# P_11__CPU_IO.net
KiCad netlist of a schematic drawn in Altium Designer
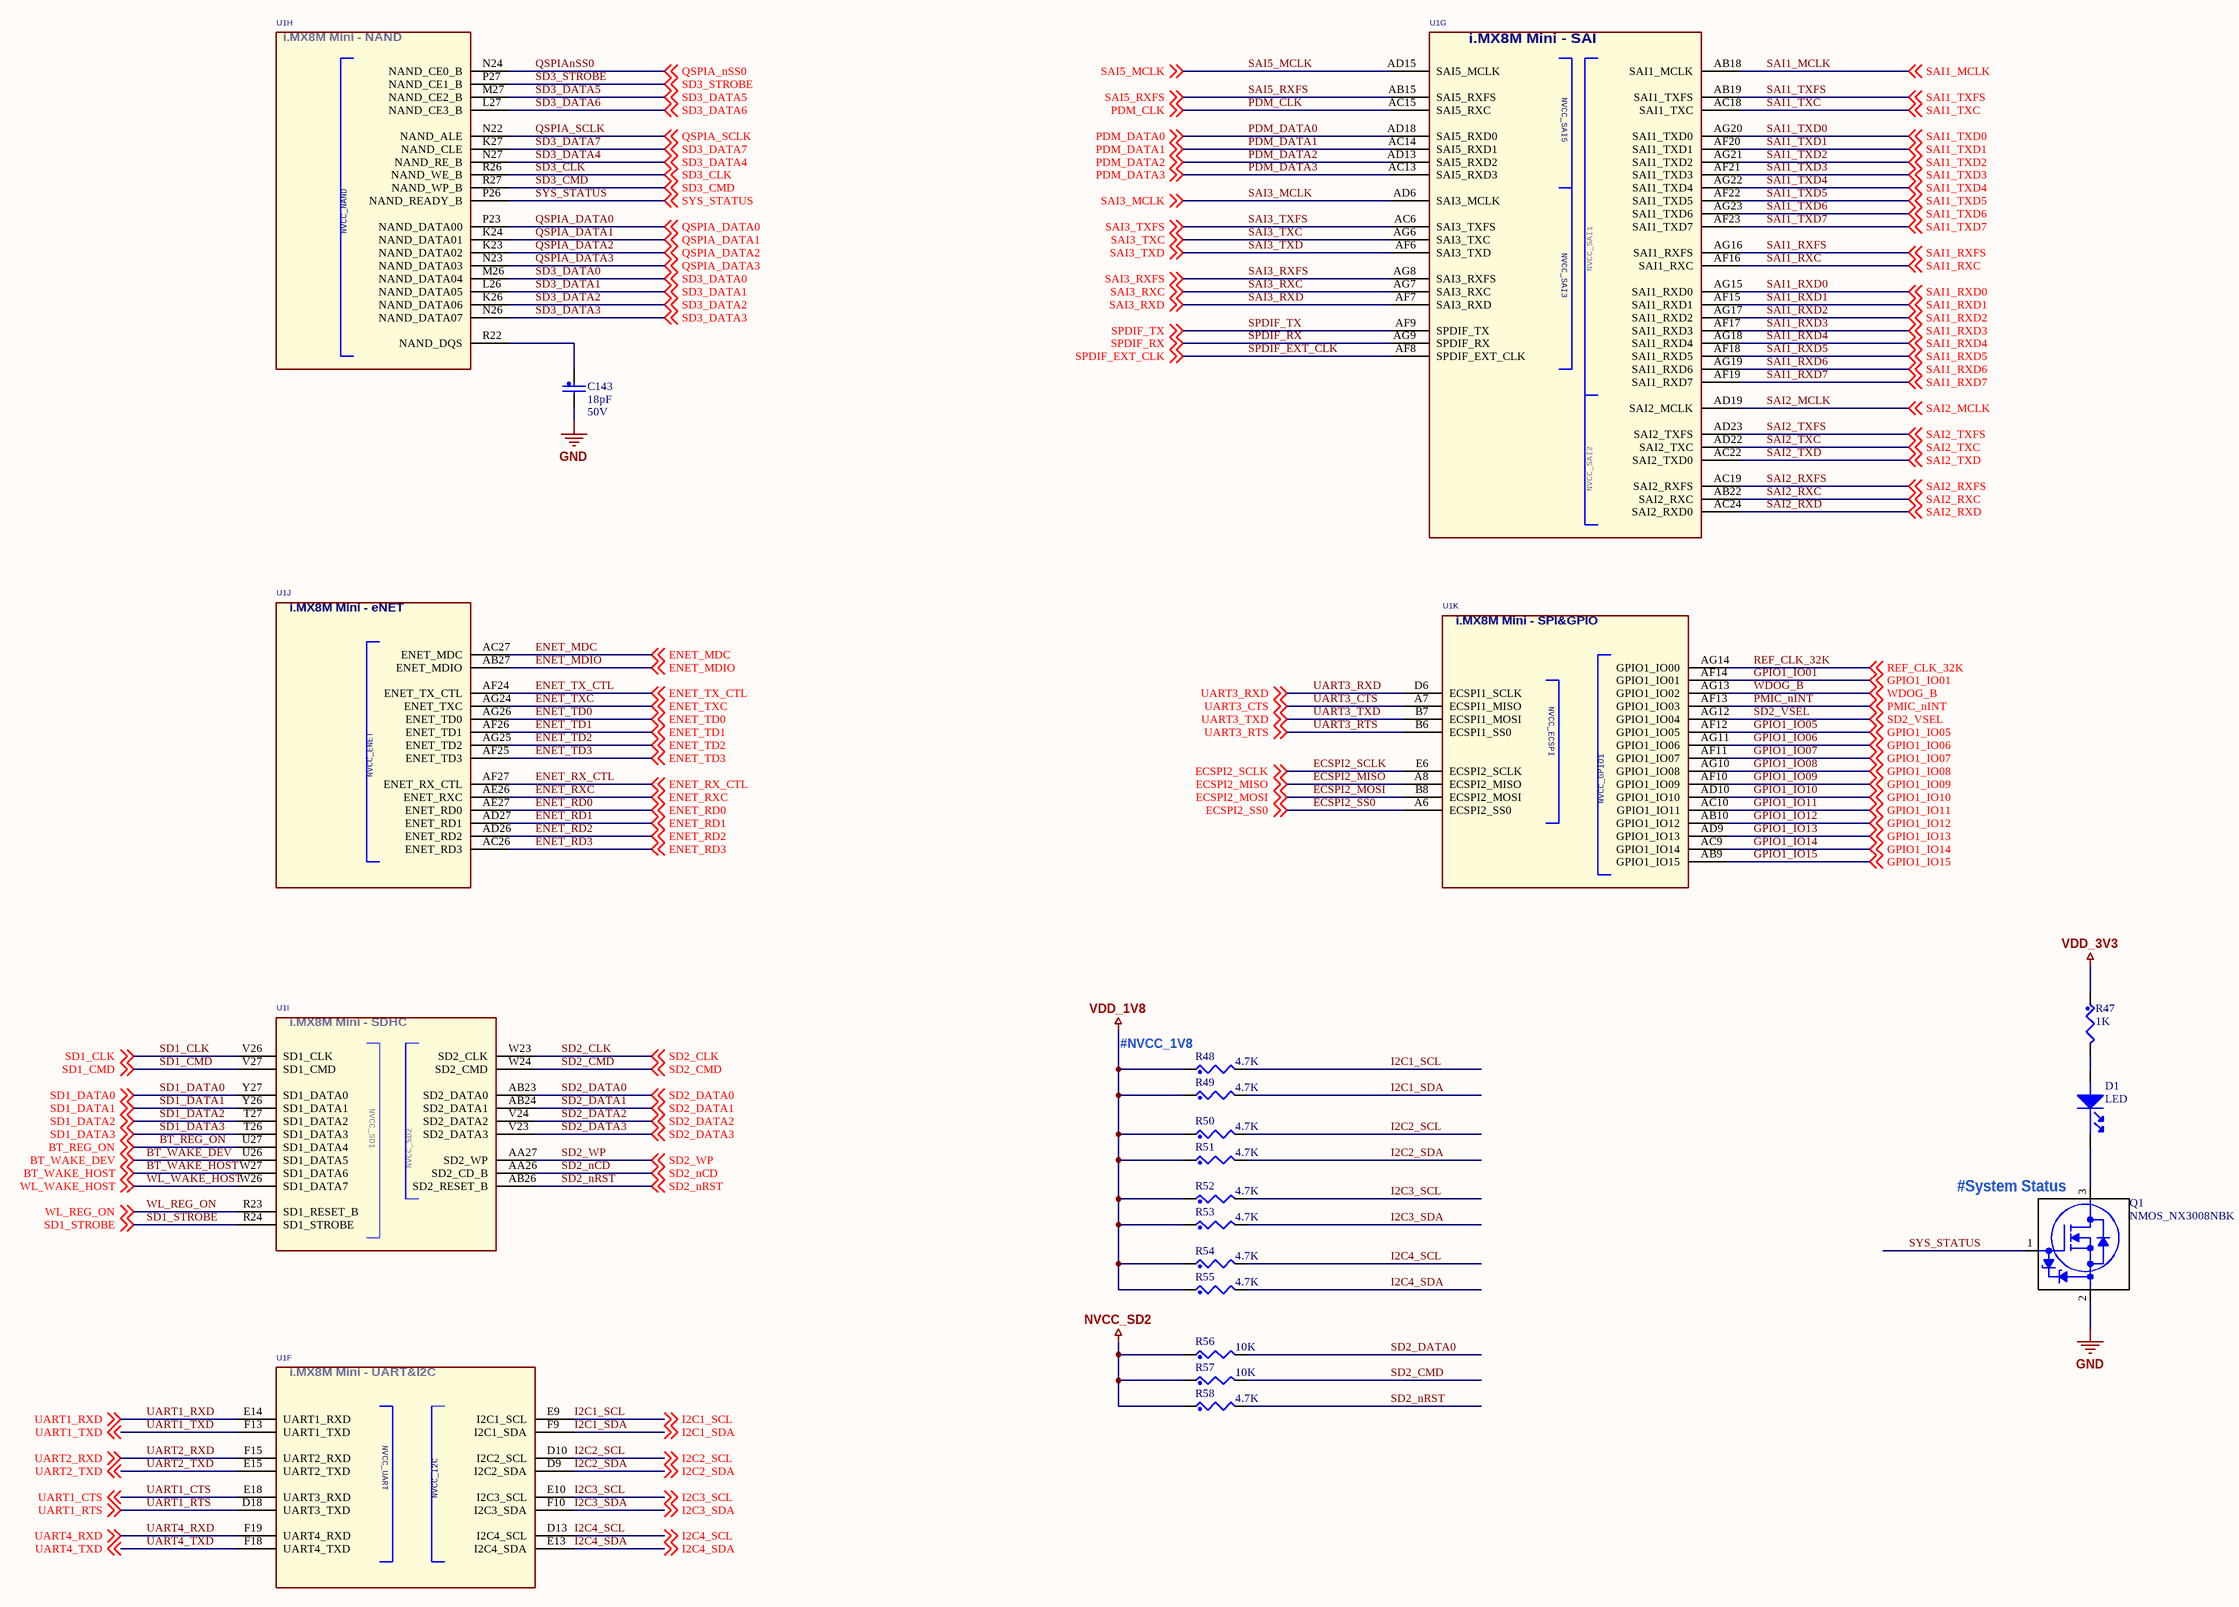
[diagram p0: P[11]_CPU_IO.SchDoc]

(export (version "E")
  (design (tool "Eeschema 10.0.6"))
  (components
    (comp (ref "C143")
      (value "18pF")
      (footprint "0201_CC - C")
      (fields (field (name "VOLTAGE") "50V"))
      (libsource (lib "AA_iMX8_M_") (part "CAP_NP"))
    )
    (comp (ref "D1") (value "LED") (footprint "LED_0603") (libsource (lib "AA_iMX8_M_") (part "LED")))
    (comp (ref "Q1")
      (value "NMOS_NX3008NBK")
      (footprint "SOT65P210X110-3N")
      (description "NMOS_NX3008NBK\\AAR")
      (libsource (lib "AA_iMX8_M_") (part "NMOS_NX3008NBK"))
    )
    (comp (ref "R47") (value "1K") (footprint "0201_CC") (libsource (lib "AA_iMX8_M_") (part "RES")))
    (comp (ref "R48") (value "4.7K") (footprint "0201_CC") (libsource (lib "AA_iMX8_M_") (part "RES")))
    (comp (ref "R49") (value "4.7K") (footprint "0201_CC") (libsource (lib "AA_iMX8_M_") (part "RES")))
    (comp (ref "R50") (value "4.7K") (footprint "0201_CC") (libsource (lib "AA_iMX8_M_") (part "RES")))
    (comp (ref "R51") (value "4.7K") (footprint "0201_CC") (libsource (lib "AA_iMX8_M_") (part "RES")))
    (comp (ref "R52") (value "4.7K") (footprint "0201_CC") (libsource (lib "AA_iMX8_M_") (part "RES")))
    (comp (ref "R53") (value "4.7K") (footprint "0201_CC") (libsource (lib "AA_iMX8_M_") (part "RES")))
    (comp (ref "R54") (value "4.7K") (footprint "0201_CC") (libsource (lib "AA_iMX8_M_") (part "RES")))
    (comp (ref "R55") (value "4.7K") (footprint "0201_CC") (libsource (lib "AA_iMX8_M_") (part "RES")))
    (comp (ref "R56") (value "10K") (footprint "0201_CC") (libsource (lib "AA_iMX8_M_") (part "RES")))
    (comp (ref "R57") (value "10K") (footprint "0201_CC") (libsource (lib "AA_iMX8_M_") (part "RES")))
    (comp (ref "R58") (value "4.7K") (footprint "0201_CC") (libsource (lib "AA_iMX8_M_") (part "RES")))
    (comp (ref "U1")
      (value "SFP_CGND")
      (footprint "BGA486_0P5_14X14")
      (description "IC CPU QUAD CORTEX A53+M4 1.8GHZ BGA486 / By Arman Arvand")
      (libsource (lib "AA_iMX8_M_") (part "MIMX8MM_BGA486P"))
    )
  )
  (nets
    (net (code "1") (name "BT_REG_ON") (class "Default")
      (node (ref "U1") (pin "U27") (pinfunction "SD1_DATA4_U27") (pintype "passive"))
    )
    (net (code "2") (name "BT_WAKE_DEV") (class "Default")
      (node (ref "U1") (pin "U26") (pinfunction "SD1_DATA5_U26") (pintype "passive"))
    )
    (net (code "3") (name "BT_WAKE_HOST") (class "Default")
      (node (ref "U1") (pin "W27") (pinfunction "SD1_DATA6_W27") (pintype "passive"))
    )
    (net (code "4") (name "ECSPI2_MISO") (class "Default")
      (node (ref "U1") (pin "A8") (pinfunction "ECSPI2_MISO_A8") (pintype "passive"))
    )
    (net (code "5") (name "ECSPI2_MOSI") (class "Default")
      (node (ref "U1") (pin "B8") (pinfunction "ECSPI2_MOSI_B8") (pintype "passive"))
    )
    (net (code "6") (name "ECSPI2_SCLK") (class "Default")
      (node (ref "U1") (pin "E6") (pinfunction "ECSPI2_SCLK_E6") (pintype "passive"))
    )
    (net (code "7") (name "ECSPI2_SS0") (class "Default")
      (node (ref "U1") (pin "A6") (pinfunction "ECSPI2_SS0_A6") (pintype "passive"))
    )
    (net (code "8") (name "ENET_MDC") (class "Default")
      (node (ref "U1") (pin "AC27") (pinfunction "ENET_MDC_AC27") (pintype "passive"))
    )
    (net (code "9") (name "ENET_MDIO") (class "Default")
      (node (ref "U1") (pin "AB27") (pinfunction "ENET_MDIO_AB27") (pintype "passive"))
    )
    (net (code "10") (name "ENET_RD0") (class "Default")
      (node (ref "U1") (pin "AE27") (pinfunction "ENET_RD0_AE27") (pintype "passive"))
    )
    (net (code "11") (name "ENET_RD1") (class "Default")
      (node (ref "U1") (pin "AD27") (pinfunction "ENET_RD1_AD27") (pintype "passive"))
    )
    (net (code "12") (name "ENET_RD2") (class "Default")
      (node (ref "U1") (pin "AD26") (pinfunction "ENET_RD2_AD26") (pintype "passive"))
    )
    (net (code "13") (name "ENET_RD3") (class "Default")
      (node (ref "U1") (pin "AC26") (pinfunction "ENET_RD3_AC26") (pintype "passive"))
    )
    (net (code "14") (name "ENET_RXC") (class "Default")
      (node (ref "U1") (pin "AE26") (pinfunction "ENET_RXC_AE26") (pintype "passive"))
    )
    (net (code "15") (name "ENET_RX_CTL") (class "Default")
      (node (ref "U1") (pin "AF27") (pinfunction "ENET_RX_CTL_AF27") (pintype "passive"))
    )
    (net (code "16") (name "ENET_TD0") (class "Default")
      (node (ref "U1") (pin "AG26") (pinfunction "ENET_TD0_AG26") (pintype "passive"))
    )
    (net (code "17") (name "ENET_TD1") (class "Default")
      (node (ref "U1") (pin "AF26") (pinfunction "ENET_TD1_AF26") (pintype "passive"))
    )
    (net (code "18") (name "ENET_TD2") (class "Default")
      (node (ref "U1") (pin "AG25") (pinfunction "ENET_TD2_AG25") (pintype "passive"))
    )
    (net (code "19") (name "ENET_TD3") (class "Default")
      (node (ref "U1") (pin "AF25") (pinfunction "ENET_TD3_AF25") (pintype "passive"))
    )
    (net (code "20") (name "ENET_TXC") (class "Default")
      (node (ref "U1") (pin "AG24") (pinfunction "ENET_TXC_AG24") (pintype "passive"))
    )
    (net (code "21") (name "ENET_TX_CTL") (class "Default")
      (node (ref "U1") (pin "AF24") (pinfunction "ENET_TX_CTL_AF24") (pintype "passive"))
    )
    (net (code "22") (name "GND") (class "Default")
      (node (ref "C143") (pin "2") (pinfunction "2_2") (pintype "passive"))
      (node (ref "Q1") (pin "2") (pinfunction "SOURCE_2") (pintype "passive"))
    )
    (net (code "23") (name "GPIO1_IO01") (class "Default")
      (node (ref "U1") (pin "AF14") (pinfunction "GPIO1_IO01_AF14") (pintype "passive"))
    )
    (net (code "24") (name "GPIO1_IO05") (class "Default")
      (node (ref "U1") (pin "AF12") (pinfunction "GPIO1_IO05_AF12") (pintype "passive"))
    )
    (net (code "25") (name "GPIO1_IO06") (class "Default")
      (node (ref "U1") (pin "AG11") (pinfunction "GPIO1_IO06_AG11") (pintype "passive"))
    )
    (net (code "26") (name "GPIO1_IO07") (class "Default")
      (node (ref "U1") (pin "AF11") (pinfunction "GPIO1_IO07_AF11") (pintype "passive"))
    )
    (net (code "27") (name "GPIO1_IO08") (class "Default")
      (node (ref "U1") (pin "AG10") (pinfunction "GPIO1_IO08_AG10") (pintype "passive"))
    )
    (net (code "28") (name "GPIO1_IO09") (class "Default")
      (node (ref "U1") (pin "AF10") (pinfunction "GPIO1_IO09_AF10") (pintype "passive"))
    )
    (net (code "29") (name "GPIO1_IO10") (class "Default")
      (node (ref "U1") (pin "AD10") (pinfunction "GPIO1_IO10_AD10") (pintype "passive"))
    )
    (net (code "30") (name "GPIO1_IO11") (class "Default")
      (node (ref "U1") (pin "AC10") (pinfunction "GPIO1_IO11_AC10") (pintype "passive"))
    )
    (net (code "31") (name "GPIO1_IO12") (class "Default")
      (node (ref "U1") (pin "AB10") (pinfunction "GPIO1_IO12_AB10") (pintype "passive"))
    )
    (net (code "32") (name "GPIO1_IO13") (class "Default")
      (node (ref "U1") (pin "AD9") (pinfunction "GPIO1_IO13_AD9") (pintype "passive"))
    )
    (net (code "33") (name "GPIO1_IO14") (class "Default")
      (node (ref "U1") (pin "AC9") (pinfunction "GPIO1_IO14_AC9") (pintype "passive"))
    )
    (net (code "34") (name "GPIO1_IO15") (class "Default")
      (node (ref "U1") (pin "AB9") (pinfunction "GPIO1_IO15_AB9") (pintype "passive"))
    )
    (net (code "35") (name "I2C1_SCL") (class "Default")
      (node (ref "R48") (pin "2") (pinfunction "2_2") (pintype "passive"))
      (node (ref "U1") (pin "E9") (pinfunction "I2C1_SCL_E9") (pintype "passive"))
    )
    (net (code "36") (name "I2C1_SDA") (class "Default")
      (node (ref "R49") (pin "2") (pinfunction "2_2") (pintype "passive"))
      (node (ref "U1") (pin "F9") (pinfunction "I2C1_SDA_F9") (pintype "passive"))
    )
    (net (code "37") (name "I2C2_SCL") (class "Default")
      (node (ref "R50") (pin "2") (pinfunction "2_2") (pintype "passive"))
      (node (ref "U1") (pin "D10") (pinfunction "I2C2_SCL_D10") (pintype "passive"))
    )
    (net (code "38") (name "I2C2_SDA") (class "Default")
      (node (ref "R51") (pin "2") (pinfunction "2_2") (pintype "passive"))
      (node (ref "U1") (pin "D9") (pinfunction "I2C2_SDA_D9") (pintype "passive"))
    )
    (net (code "39") (name "I2C3_SCL") (class "Default")
      (node (ref "R52") (pin "2") (pinfunction "2_2") (pintype "passive"))
      (node (ref "U1") (pin "E10") (pinfunction "I2C3_SCL_E10") (pintype "passive"))
    )
    (net (code "40") (name "I2C3_SDA") (class "Default")
      (node (ref "R53") (pin "2") (pinfunction "2_2") (pintype "passive"))
      (node (ref "U1") (pin "F10") (pinfunction "I2C3_SDA_F10") (pintype "passive"))
    )
    (net (code "41") (name "I2C4_SCL") (class "Default")
      (node (ref "R54") (pin "2") (pinfunction "2_2") (pintype "passive"))
      (node (ref "U1") (pin "D13") (pinfunction "I2C4_SCL_D13") (pintype "passive"))
    )
    (net (code "42") (name "I2C4_SDA") (class "Default")
      (node (ref "R55") (pin "2") (pinfunction "2_2") (pintype "passive"))
      (node (ref "U1") (pin "E13") (pinfunction "I2C4_SDA_E13") (pintype "passive"))
    )
    (net (code "43") (name "NVCC_SD2") (class "Default")
      (node (ref "R56") (pin "1") (pinfunction "1_1") (pintype "passive"))
      (node (ref "R57") (pin "1") (pinfunction "1_1") (pintype "passive"))
      (node (ref "R58") (pin "1") (pinfunction "1_1") (pintype "passive"))
    )
    (net (code "44") (name "Net-(D1-ANODE)") (class "Default")
      (node (ref "D1") (pin "A") (pinfunction "ANODE_A") (pintype "passive"))
      (node (ref "R47") (pin "2") (pinfunction "2_2") (pintype "passive"))
    )
    (net (code "45") (name "Net-(D1-CATHODE)") (class "Default")
      (node (ref "D1") (pin "C") (pinfunction "CATHODE_C") (pintype "passive"))
      (node (ref "Q1") (pin "3") (pinfunction "DRAIN_3") (pintype "passive"))
    )
    (net (code "46") (name "Net-(U1H-NAND_DQS)") (class "Default")
      (node (ref "C143") (pin "1") (pinfunction "1_1") (pintype "passive"))
      (node (ref "U1") (pin "R22") (pinfunction "NAND_DQS_R22") (pintype "passive"))
    )
    (net (code "47") (name "PDM_CLK") (class "Default")
      (node (ref "U1") (pin "AC15") (pinfunction "SAI5_RXC_AC15") (pintype "passive"))
    )
    (net (code "48") (name "PDM_DATA0") (class "Default")
      (node (ref "U1") (pin "AD18") (pinfunction "SAI5_RXD0_AD18") (pintype "passive"))
    )
    (net (code "49") (name "PDM_DATA1") (class "Default")
      (node (ref "U1") (pin "AC14") (pinfunction "SAI5_RXD1_AC14") (pintype "passive"))
    )
    (net (code "50") (name "PDM_DATA2") (class "Default")
      (node (ref "U1") (pin "AD13") (pinfunction "SAI5_RXD2_AD13") (pintype "passive"))
    )
    (net (code "51") (name "PDM_DATA3") (class "Default")
      (node (ref "U1") (pin "AC13") (pinfunction "SAI5_RXD3_AC13") (pintype "passive"))
    )
    (net (code "52") (name "PMIC_nINT") (class "Default")
      (node (ref "U1") (pin "AF13") (pinfunction "GPIO1_IO03_AF13") (pintype "passive"))
    )
    (net (code "53") (name "QSPIA_DATA0") (class "Default")
      (node (ref "U1") (pin "P23") (pinfunction "NAND_DATA00_P23") (pintype "passive"))
    )
    (net (code "54") (name "QSPIA_DATA1") (class "Default")
      (node (ref "U1") (pin "K24") (pinfunction "NAND_DATA01_K24") (pintype "passive"))
    )
    (net (code "55") (name "QSPIA_DATA2") (class "Default")
      (node (ref "U1") (pin "K23") (pinfunction "NAND_DATA02_K23") (pintype "passive"))
    )
    (net (code "56") (name "QSPIA_DATA3") (class "Default")
      (node (ref "U1") (pin "N23") (pinfunction "NAND_DATA03_N23") (pintype "passive"))
    )
    (net (code "57") (name "QSPIA_SCLK") (class "Default")
      (node (ref "U1") (pin "N22") (pinfunction "NAND_ALE_N22") (pintype "passive"))
    )
    (net (code "58") (name "QSPIA_nSS0") (class "Default")
      (node (ref "U1") (pin "N24") (pinfunction "NAND_CE0_B_N24") (pintype "passive"))
    )
    (net (code "59") (name "REF_CLK_32K") (class "Default")
      (node (ref "U1") (pin "AG14") (pinfunction "GPIO1_IO00_AG14") (pintype "passive"))
    )
    (net (code "60") (name "SAI1_MCLK") (class "Default")
      (node (ref "U1") (pin "AB18") (pinfunction "SAI1_MCLK_AB18") (pintype "passive"))
    )
    (net (code "61") (name "SAI1_RXC") (class "Default")
      (node (ref "U1") (pin "AF16") (pinfunction "SAI1_RXC_AF16") (pintype "passive"))
    )
    (net (code "62") (name "SAI1_RXD0") (class "Default")
      (node (ref "U1") (pin "AG15") (pinfunction "SAI1_RXD0_AG15") (pintype "passive"))
    )
    (net (code "63") (name "SAI1_RXD1") (class "Default")
      (node (ref "U1") (pin "AF15") (pinfunction "SAI1_RXD1_AF15") (pintype "passive"))
    )
    (net (code "64") (name "SAI1_RXD2") (class "Default")
      (node (ref "U1") (pin "AG17") (pinfunction "SAI1_RXD2_AG17") (pintype "passive"))
    )
    (net (code "65") (name "SAI1_RXD3") (class "Default")
      (node (ref "U1") (pin "AF17") (pinfunction "SAI1_RXD3_AF17") (pintype "passive"))
    )
    (net (code "66") (name "SAI1_RXD4") (class "Default")
      (node (ref "U1") (pin "AG18") (pinfunction "SAI1_RXD4_AG18") (pintype "passive"))
    )
    (net (code "67") (name "SAI1_RXD5") (class "Default")
      (node (ref "U1") (pin "AF18") (pinfunction "SAI1_RXD5_AF18") (pintype "passive"))
    )
    (net (code "68") (name "SAI1_RXD6") (class "Default")
      (node (ref "U1") (pin "AG19") (pinfunction "SAI1_RXD6_AG19") (pintype "passive"))
    )
    (net (code "69") (name "SAI1_RXD7") (class "Default")
      (node (ref "U1") (pin "AF19") (pinfunction "SAI1_RXD7_AF19") (pintype "passive"))
    )
    (net (code "70") (name "SAI1_RXFS") (class "Default")
      (node (ref "U1") (pin "AG16") (pinfunction "SAI1_RXFS_AG16") (pintype "passive"))
    )
    (net (code "71") (name "SAI1_TXC") (class "Default")
      (node (ref "U1") (pin "AC18") (pinfunction "SAI1_TXC_AC18") (pintype "passive"))
    )
    (net (code "72") (name "SAI1_TXD0") (class "Default")
      (node (ref "U1") (pin "AG20") (pinfunction "SAI1_TXD0_AG20") (pintype "passive"))
    )
    (net (code "73") (name "SAI1_TXD1") (class "Default")
      (node (ref "U1") (pin "AF20") (pinfunction "SAI1_TXD1_AF20") (pintype "passive"))
    )
    (net (code "74") (name "SAI1_TXD2") (class "Default")
      (node (ref "U1") (pin "AG21") (pinfunction "SAI1_TXD2_AG21") (pintype "passive"))
    )
    (net (code "75") (name "SAI1_TXD3") (class "Default")
      (node (ref "U1") (pin "AF21") (pinfunction "SAI1_TXD3_AF21") (pintype "passive"))
    )
    (net (code "76") (name "SAI1_TXD4") (class "Default")
      (node (ref "U1") (pin "AG22") (pinfunction "SAI1_TXD4_AG22") (pintype "passive"))
    )
    (net (code "77") (name "SAI1_TXD5") (class "Default")
      (node (ref "U1") (pin "AF22") (pinfunction "SAI1_TXD5_AF22") (pintype "passive"))
    )
    (net (code "78") (name "SAI1_TXD6") (class "Default")
      (node (ref "U1") (pin "AG23") (pinfunction "SAI1_TXD6_AG23") (pintype "passive"))
    )
    (net (code "79") (name "SAI1_TXD7") (class "Default")
      (node (ref "U1") (pin "AF23") (pinfunction "SAI1_TXD7_AF23") (pintype "passive"))
    )
    (net (code "80") (name "SAI1_TXFS") (class "Default")
      (node (ref "U1") (pin "AB19") (pinfunction "SAI1_TXFS_AB19") (pintype "passive"))
    )
    (net (code "81") (name "SAI2_MCLK") (class "Default")
      (node (ref "U1") (pin "AD19") (pinfunction "SAI2_MCLK_AD19") (pintype "passive"))
    )
    (net (code "82") (name "SAI2_RXC") (class "Default")
      (node (ref "U1") (pin "AB22") (pinfunction "SAI2_RXC_AB22") (pintype "passive"))
    )
    (net (code "83") (name "SAI2_RXD") (class "Default")
      (node (ref "U1") (pin "AC24") (pinfunction "SAI2_RXD0_AC24") (pintype "passive"))
    )
    (net (code "84") (name "SAI2_RXFS") (class "Default")
      (node (ref "U1") (pin "AC19") (pinfunction "SAI2_RXFS_AC19") (pintype "passive"))
    )
    (net (code "85") (name "SAI2_TXC") (class "Default")
      (node (ref "U1") (pin "AD22") (pinfunction "SAI2_TXC_AD22") (pintype "passive"))
    )
    (net (code "86") (name "SAI2_TXD") (class "Default")
      (node (ref "U1") (pin "AC22") (pinfunction "SAI2_TXD0_AC22") (pintype "passive"))
    )
    (net (code "87") (name "SAI2_TXFS") (class "Default")
      (node (ref "U1") (pin "AD23") (pinfunction "SAI2_TXFS_AD23") (pintype "passive"))
    )
    (net (code "88") (name "SAI3_MCLK") (class "Default")
      (node (ref "U1") (pin "AD6") (pinfunction "SAI3_MCLK_AD6") (pintype "passive"))
    )
    (net (code "89") (name "SAI3_RXC") (class "Default")
      (node (ref "U1") (pin "AG7") (pinfunction "SAI3_RXC_AG7") (pintype "passive"))
    )
    (net (code "90") (name "SAI3_RXD") (class "Default")
      (node (ref "U1") (pin "AF7") (pinfunction "SAI3_RXD_AF7") (pintype "passive"))
    )
    (net (code "91") (name "SAI3_RXFS") (class "Default")
      (node (ref "U1") (pin "AG8") (pinfunction "SAI3_RXFS_AG8") (pintype "passive"))
    )
    (net (code "92") (name "SAI3_TXC") (class "Default")
      (node (ref "U1") (pin "AG6") (pinfunction "SAI3_TXC_AG6") (pintype "passive"))
    )
    (net (code "93") (name "SAI3_TXD") (class "Default")
      (node (ref "U1") (pin "AF6") (pinfunction "SAI3_TXD_AF6") (pintype "passive"))
    )
    (net (code "94") (name "SAI3_TXFS") (class "Default")
      (node (ref "U1") (pin "AC6") (pinfunction "SAI3_TXFS_AC6") (pintype "passive"))
    )
    (net (code "95") (name "SAI5_MCLK") (class "Default")
      (node (ref "U1") (pin "AD15") (pinfunction "SAI5_MCLK_AD15") (pintype "passive"))
    )
    (net (code "96") (name "SAI5_RXFS") (class "Default")
      (node (ref "U1") (pin "AB15") (pinfunction "SAI5_RXFS_AB15") (pintype "passive"))
    )
    (net (code "97") (name "SD1_CLK") (class "Default")
      (node (ref "U1") (pin "V26") (pinfunction "SD1_CLK_V26") (pintype "passive"))
    )
    (net (code "98") (name "SD1_CMD") (class "Default")
      (node (ref "U1") (pin "V27") (pinfunction "SD1_CMD_V27") (pintype "passive"))
    )
    (net (code "99") (name "SD1_DATA0") (class "Default")
      (node (ref "U1") (pin "Y27") (pinfunction "SD1_DATA0_Y27") (pintype "passive"))
    )
    (net (code "100") (name "SD1_DATA1") (class "Default")
      (node (ref "U1") (pin "Y26") (pinfunction "SD1_DATA1_Y26") (pintype "passive"))
    )
    (net (code "101") (name "SD1_DATA2") (class "Default")
      (node (ref "U1") (pin "T27") (pinfunction "SD1_DATA2_T27") (pintype "passive"))
    )
    (net (code "102") (name "SD1_DATA3") (class "Default")
      (node (ref "U1") (pin "T26") (pinfunction "SD1_DATA3_T26") (pintype "passive"))
    )
    (net (code "103") (name "SD1_STROBE") (class "Default")
      (node (ref "U1") (pin "R24") (pinfunction "SD1_STROBE_R24") (pintype "passive"))
    )
    (net (code "104") (name "SD2_CLK") (class "Default")
      (node (ref "U1") (pin "W23") (pinfunction "SD2_CLK_W23") (pintype "passive"))
    )
    (net (code "105") (name "SD2_CMD") (class "Default")
      (node (ref "R57") (pin "2") (pinfunction "2_2") (pintype "passive"))
      (node (ref "U1") (pin "W24") (pinfunction "SD2_CMD_W24") (pintype "passive"))
    )
    (net (code "106") (name "SD2_DATA0") (class "Default")
      (node (ref "R56") (pin "2") (pinfunction "2_2") (pintype "passive"))
      (node (ref "U1") (pin "AB23") (pinfunction "SD2_DATA0_AB23") (pintype "passive"))
    )
    (net (code "107") (name "SD2_DATA1") (class "Default")
      (node (ref "U1") (pin "AB24") (pinfunction "SD2_DATA1_AB24") (pintype "passive"))
    )
    (net (code "108") (name "SD2_DATA2") (class "Default")
      (node (ref "U1") (pin "V24") (pinfunction "SD2_DATA2_V24") (pintype "passive"))
    )
    (net (code "109") (name "SD2_DATA3") (class "Default")
      (node (ref "U1") (pin "V23") (pinfunction "SD2_DATA3_V23") (pintype "passive"))
    )
    (net (code "110") (name "SD2_VSEL") (class "Default")
      (node (ref "U1") (pin "AG12") (pinfunction "GPIO1_IO04_AG12") (pintype "passive"))
    )
    (net (code "111") (name "SD2_WP") (class "Default")
      (node (ref "U1") (pin "AA27") (pinfunction "SD2_WP_AA27") (pintype "passive"))
    )
    (net (code "112") (name "SD2_nCD") (class "Default")
      (node (ref "U1") (pin "AA26") (pinfunction "SD2_CD_B_AA26") (pintype "passive"))
    )
    (net (code "113") (name "SD2_nRST") (class "Default")
      (node (ref "R58") (pin "2") (pinfunction "2_2") (pintype "passive"))
      (node (ref "U1") (pin "AB26") (pinfunction "SD2_RESET_B_AB26") (pintype "passive"))
    )
    (net (code "114") (name "SD3_CLK") (class "Default")
      (node (ref "U1") (pin "R26") (pinfunction "NAND_WE_B_R26") (pintype "passive"))
    )
    (net (code "115") (name "SD3_CMD") (class "Default")
      (node (ref "U1") (pin "R27") (pinfunction "NAND_WP_B_R27") (pintype "passive"))
    )
    (net (code "116") (name "SD3_DATA0") (class "Default")
      (node (ref "U1") (pin "M26") (pinfunction "NAND_DATA04_M26") (pintype "passive"))
    )
    (net (code "117") (name "SD3_DATA1") (class "Default")
      (node (ref "U1") (pin "L26") (pinfunction "NAND_DATA05_L26") (pintype "passive"))
    )
    (net (code "118") (name "SD3_DATA2") (class "Default")
      (node (ref "U1") (pin "K26") (pinfunction "NAND_DATA06_K26") (pintype "passive"))
    )
    (net (code "119") (name "SD3_DATA3") (class "Default")
      (node (ref "U1") (pin "N26") (pinfunction "NAND_DATA07_N26") (pintype "passive"))
    )
    (net (code "120") (name "SD3_DATA4") (class "Default")
      (node (ref "U1") (pin "N27") (pinfunction "NAND_RE_B_N27") (pintype "passive"))
    )
    (net (code "121") (name "SD3_DATA5") (class "Default")
      (node (ref "U1") (pin "M27") (pinfunction "NAND_CE2_B_M27") (pintype "passive"))
    )
    (net (code "122") (name "SD3_DATA6") (class "Default")
      (node (ref "U1") (pin "L27") (pinfunction "NAND_CE3_B_L27") (pintype "passive"))
    )
    (net (code "123") (name "SD3_DATA7") (class "Default")
      (node (ref "U1") (pin "K27") (pinfunction "NAND_CLE_K27") (pintype "passive"))
    )
    (net (code "124") (name "SD3_STROBE") (class "Default")
      (node (ref "U1") (pin "P27") (pinfunction "NAND_CE1_B_P27") (pintype "passive"))
    )
    (net (code "125") (name "SPDIF_EXT_CLK") (class "Default")
      (node (ref "U1") (pin "AF8") (pinfunction "SPDIF_EXT_CLK_AF8") (pintype "passive"))
    )
    (net (code "126") (name "SPDIF_RX") (class "Default")
      (node (ref "U1") (pin "AG9") (pinfunction "SPDIF_RX_AG9") (pintype "passive"))
    )
    (net (code "127") (name "SPDIF_TX") (class "Default")
      (node (ref "U1") (pin "AF9") (pinfunction "SPDIF_TX_AF9") (pintype "passive"))
    )
    (net (code "128") (name "SYS_STATUS") (class "Default")
      (node (ref "Q1") (pin "1") (pinfunction "GATE_1") (pintype "passive"))
      (node (ref "U1") (pin "P26") (pinfunction "NAND_READY_B_P26") (pintype "passive"))
    )
    (net (code "129") (name "UART1_CTS") (class "Default")
      (node (ref "U1") (pin "E18") (pinfunction "UART3_RXD_E18") (pintype "passive"))
    )
    (net (code "130") (name "UART1_RTS") (class "Default")
      (node (ref "U1") (pin "D18") (pinfunction "UART3_TXD_D18") (pintype "passive"))
    )
    (net (code "131") (name "UART1_RXD") (class "Default")
      (node (ref "U1") (pin "E14") (pinfunction "UART1_RXD_E14") (pintype "passive"))
    )
    (net (code "132") (name "UART1_TXD") (class "Default")
      (node (ref "U1") (pin "F13") (pinfunction "UART1_TXD_F13") (pintype "passive"))
    )
    (net (code "133") (name "UART2_RXD") (class "Default")
      (node (ref "U1") (pin "F15") (pinfunction "UART2_RXD_F15") (pintype "passive"))
    )
    (net (code "134") (name "UART2_TXD") (class "Default")
      (node (ref "U1") (pin "E15") (pinfunction "UART2_TXD_E15") (pintype "passive"))
    )
    (net (code "135") (name "UART3_CTS") (class "Default")
      (node (ref "U1") (pin "A7") (pinfunction "ECSPI1_MISO_A7") (pintype "passive"))
    )
    (net (code "136") (name "UART3_RTS") (class "Default")
      (node (ref "U1") (pin "B6") (pinfunction "ECSPI1_SS0_B6") (pintype "passive"))
    )
    (net (code "137") (name "UART3_RXD") (class "Default")
      (node (ref "U1") (pin "D6") (pinfunction "ECSPI1_SCLK_D6") (pintype "passive"))
    )
    (net (code "138") (name "UART3_TXD") (class "Default")
      (node (ref "U1") (pin "B7") (pinfunction "ECSPI1_MOSI_B7") (pintype "passive"))
    )
    (net (code "139") (name "UART4_RXD") (class "Default")
      (node (ref "U1") (pin "F19") (pinfunction "UART4_RXD_F19") (pintype "passive"))
    )
    (net (code "140") (name "UART4_TXD") (class "Default")
      (node (ref "U1") (pin "F18") (pinfunction "UART4_TXD_F18") (pintype "passive"))
    )
    (net (code "141") (name "VDD_1V8") (class "Default")
      (node (ref "R48") (pin "1") (pinfunction "1_1") (pintype "passive"))
      (node (ref "R49") (pin "1") (pinfunction "1_1") (pintype "passive"))
      (node (ref "R50") (pin "1") (pinfunction "1_1") (pintype "passive"))
      (node (ref "R51") (pin "1") (pinfunction "1_1") (pintype "passive"))
      (node (ref "R52") (pin "1") (pinfunction "1_1") (pintype "passive"))
      (node (ref "R53") (pin "1") (pinfunction "1_1") (pintype "passive"))
      (node (ref "R54") (pin "1") (pinfunction "1_1") (pintype "passive"))
      (node (ref "R55") (pin "1") (pinfunction "1_1") (pintype "passive"))
    )
    (net (code "142") (name "VDD_3V3") (class "Default")
      (node (ref "R47") (pin "1") (pinfunction "1_1") (pintype "passive"))
    )
    (net (code "143") (name "WDOG_B") (class "Default")
      (node (ref "U1") (pin "AG13") (pinfunction "GPIO1_IO02_AG13") (pintype "passive"))
    )
    (net (code "144") (name "WL_REG_ON") (class "Default")
      (node (ref "U1") (pin "R23") (pinfunction "SD1_RESET_B_R23") (pintype "passive"))
    )
    (net (code "145") (name "WL_WAKE_HOST") (class "Default")
      (node (ref "U1") (pin "W26") (pinfunction "SD1_DATA7_W26") (pintype "passive"))
    )
  )
)
